# MCU_RF.net
KiCad netlist of a schematic drawn in Altium Designer
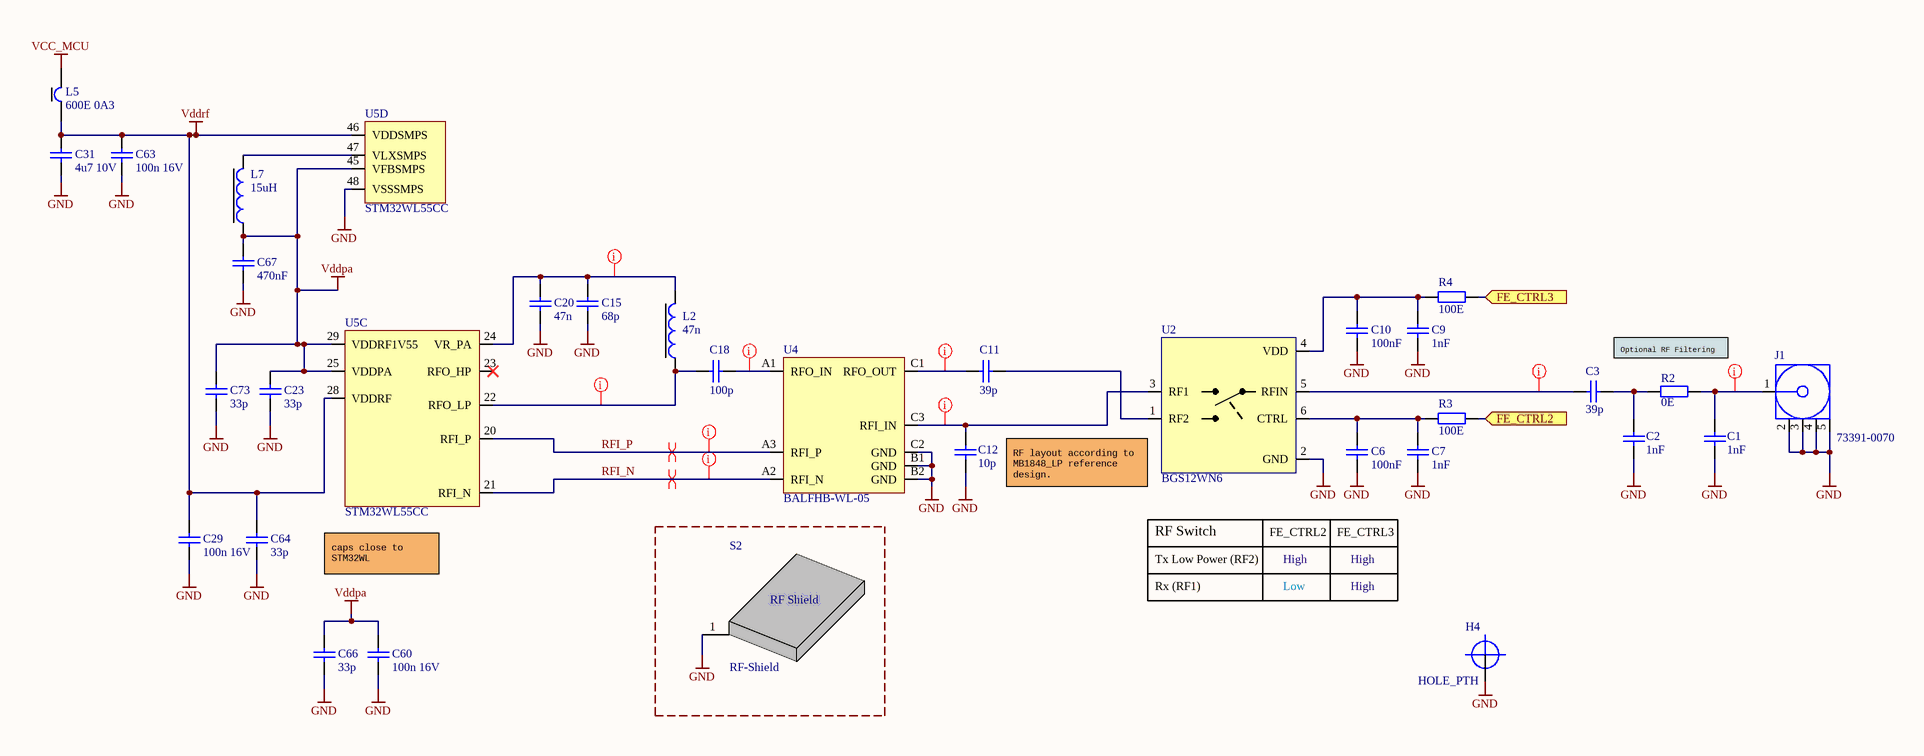
[diagram p0: MCU_RF.SchDoc]

(export (version "E")
  (design (tool "Eeschema 10.0.6"))
  (components
    (comp (ref "C1")
      (value "1nF")
      (footprint "CAP-000G001-002")
      (description "1nF 50V 10% X7R")
      (libsource (lib "DCI") (part "Capacitor_NP"))
    )
    (comp (ref "C2")
      (value "1nF")
      (footprint "CAP-000G001-002")
      (description "1nF 50V 10% X7R")
      (libsource (lib "DCI") (part "Capacitor_NP"))
    )
    (comp (ref "C3")
      (value "39p")
      (footprint "CAP-000G001-002")
      (description "39pF, 50V, 10%")
      (libsource (lib "DCI") (part "Capacitor_NP"))
    )
    (comp (ref "C6")
      (value "100nF")
      (footprint "CAP-000G001-002")
      (description "100nF, 10V, X5R")
      (libsource (lib "DCI") (part "Capacitor_NP"))
    )
    (comp (ref "C7")
      (value "1nF")
      (footprint "CAP-000G001-002")
      (description "1nF 50V 10% X7R")
      (libsource (lib "DCI") (part "Capacitor_NP"))
    )
    (comp (ref "C9")
      (value "1nF")
      (footprint "CAP-000G001-002")
      (description "1nF 50V 10% X7R")
      (libsource (lib "DCI") (part "Capacitor_NP"))
    )
    (comp (ref "C10")
      (value "100nF")
      (footprint "CAP-000G001-002")
      (description "100nF, 10V, X5R")
      (libsource (lib "DCI") (part "Capacitor_NP"))
    )
    (comp (ref "C11")
      (value "39p")
      (footprint "CAP-000G001-002")
      (description "39pF, 50V, 10%")
      (libsource (lib "DCI") (part "Capacitor_NP"))
    )
    (comp (ref "C12")
      (value "10p")
      (footprint "CAP-000G001-002")
      (description "10pF 50V 5% C0G/NP0")
      (libsource (lib "") (part "Capacitor_NP_1"))
    )
    (comp (ref "C15")
      (value "68p")
      (footprint "Cap-000G002-002")
      (description "68p 5% 25V C0G NP0")
      (libsource (lib "DCI") (part "Capacitor_NP"))
    )
    (comp (ref "C18")
      (value "100p")
      (footprint "CAP-000G001-002")
      (description "100pF, 50V, C0G")
      (libsource (lib "DCI") (part "Capacitor_NP"))
    )
    (comp (ref "C20")
      (value "47n")
      (footprint "Cap-000G002-002")
      (description "47NF, 50V, 10%")
      (libsource (lib "DCI") (part "Capacitor_NP"))
    )
    (comp (ref "C23")
      (value "33p")
      (footprint "CAP-000G001-002")
      (description "33pF, 25V, 5%")
      (libsource (lib "DCI") (part "Capacitor_NP"))
    )
    (comp (ref "C29")
      (value "100n 16V")
      (footprint "CAPC1005X05N")
      (description "100nF, 16V, 10%, X7R")
      (libsource (lib "DCI") (part "Capacitor_NP"))
    )
    (comp (ref "C31")
      (value "4u7 10V")
      (footprint "CAPC1608X09N")
      (description "4.7uF 10% 10V X5R")
      (libsource (lib "DCI") (part "Capacitor_NP"))
    )
    (comp (ref "C60")
      (value "100n 16V")
      (footprint "CAPC1005X05N")
      (description "100nF, 16V, 10%, X7R")
      (libsource (lib "DCI") (part "Capacitor_NP"))
    )
    (comp (ref "C63")
      (value "100n 16V")
      (footprint "CAPC1005X05N")
      (description "100nF, 16V, 10%, X7R")
      (libsource (lib "DCI") (part "Capacitor_NP"))
    )
    (comp (ref "C64")
      (value "33p")
      (footprint "CAP-000G001-002")
      (description "33pF, 25V, 5%")
      (libsource (lib "DCI") (part "Capacitor_NP"))
    )
    (comp (ref "C66")
      (value "33p")
      (footprint "CAP-000G001-002")
      (description "33pF, 25V, 5%")
      (libsource (lib "DCI") (part "Capacitor_NP"))
    )
    (comp (ref "C67")
      (value "470nF")
      (footprint "CAPC1608X09N")
      (description "470nF 16V ±10% X5R")
      (libsource (lib "DCI") (part "Capacitor_NP"))
    )
    (comp (ref "C73")
      (value "33p")
      (footprint "CAP-000G001-002")
      (description "33pF, 25V, 5%")
      (libsource (lib "DCI") (part "Capacitor_NP"))
    )
    (comp (ref "H4")
      (value "HOLE_PTH")
      (footprint "PTH_0.8_1.5")
      (libsource (lib "PCBComponenten") (part "HOLE_PTH"))
    )
    (comp (ref "J1")
      (value "73391-0070")
      (footprint "AMP-SMA-132134")
      (description "SMA Fem PCB vertical")
      (libsource (lib "DCI") (part "CN-1P-F-RF5"))
    )
    (comp (ref "L2")
      (value "47n")
      (footprint "IND-000G002-002")
      (description "47n 2% 210mA")
      (libsource (lib "DCI") (part "Inductor"))
    )
    (comp (ref "L5")
      (value "600E 0A3")
      (footprint "INDC1608X10N")
      (description "600E @100Mhz 0.3A")
      (libsource (lib "DCI") (part "ferrite"))
    )
    (comp (ref "L7")
      (value "15uH")
      (footprint "IND-000G004-002")
      (description "15uH 120mA")
      (libsource (lib "DCI") (part "Inductor"))
    )
    (comp (ref "R2")
      (value "0E")
      (footprint "RES-000G001-002")
      (description "0E 0.05W 1%")
      (libsource (lib "") (part "Resistor_1"))
    )
    (comp (ref "R3")
      (value "100E")
      (footprint "RES-000G001-002")
      (description "100E 0.05W 5% 100ppm")
      (libsource (lib "DCI") (part "Resistor"))
    )
    (comp (ref "R4")
      (value "100E")
      (footprint "RES-000G001-002")
      (description "100E 0.05W 5% 100ppm")
      (libsource (lib "DCI") (part "Resistor"))
    )
    (comp (ref "S2")
      (value "RF-Shield")
      (footprint "SHLD-000G000")
      (description "PCB SMD shield")
      (fields
        (field (name "MANUFACTURER") "Masach Tech")
        (field (name "MANUFACTURER_PART_NUMBER") "MS409-10")
      )
      (libsource (lib "DCI") (part "RF-Shield"))
    )
    (comp (ref "U2")
      (value "BGS12WN6")
      (footprint "DFN-400G001-006")
      (description "RF-switch")
      (fields (field (name "MANUFACTURER_PART_NUMBER") "BGS12SN6") (field (name "MANUFACTURER") "INFINEON"))
      (libsource (lib "DCI") (part "IC_BGS12SN6_PG-TSNP-6-1"))
    )
    (comp (ref "U4")
      (value "BALFHB-WL-05")
      (footprint "BGA-690G001-008")
      (description "Balun")
      (fields
        (field (name "MANUFACTURER") "STMICROELECTRONICS")
        (field (name "MANUFACTURER_PART_NUMBER") "IPD STM STM32WL")
      )
      (libsource (lib "DCI") (part "balun_BALFHB-WL-05D3"))
    )
    (comp (ref "U5")
      (value "STM32WL55CC")
      (footprint "QFN-500G000-048")
      (libsource (lib "DCI") (part "STM32WL55"))
    )
  )
  (nets
    (net (code "1") (name "/FE_CTRL2") (class "Default")
      (node (ref "R3") (pin "2") (pinfunction "2_2") (pintype "passive"))
    )
    (net (code "2") (name "/FE_CTRL3") (class "Default")
      (node (ref "R4") (pin "2") (pinfunction "2_2") (pintype "passive"))
    )
    (net (code "3") (name "/RFI_N") (class "Default")
      (node (ref "U4") (pin "A2") (pinfunction "RFI_N_A2") (pintype "passive"))
      (node (ref "U5") (pin "21") (pinfunction "RFI_N_21") (pintype "passive"))
    )
    (net (code "4") (name "/RFI_P") (class "Default")
      (node (ref "U4") (pin "A3") (pinfunction "RFI_P_A3") (pintype "passive"))
      (node (ref "U5") (pin "20") (pinfunction "RFI_P_20") (pintype "passive"))
    )
    (net (code "5") (name "GND") (class "Default")
      (node (ref "C1") (pin "1") (pinfunction "1_1") (pintype "passive"))
      (node (ref "C10") (pin "1") (pinfunction "1_1") (pintype "passive"))
      (node (ref "C12") (pin "1") (pinfunction "1_1") (pintype "passive"))
      (node (ref "C15") (pin "1") (pinfunction "1_1") (pintype "passive"))
      (node (ref "C2") (pin "1") (pinfunction "1_1") (pintype "passive"))
      (node (ref "C20") (pin "1") (pinfunction "1_1") (pintype "passive"))
      (node (ref "C23") (pin "1") (pinfunction "1_1") (pintype "passive"))
      (node (ref "C29") (pin "1") (pinfunction "1_1") (pintype "passive"))
      (node (ref "C31") (pin "1") (pinfunction "1_1") (pintype "passive"))
      (node (ref "C6") (pin "1") (pinfunction "1_1") (pintype "passive"))
      (node (ref "C60") (pin "1") (pinfunction "1_1") (pintype "passive"))
      (node (ref "C63") (pin "1") (pinfunction "1_1") (pintype "passive"))
      (node (ref "C64") (pin "1") (pinfunction "1_1") (pintype "passive"))
      (node (ref "C66") (pin "1") (pinfunction "1_1") (pintype "passive"))
      (node (ref "C67") (pin "1") (pinfunction "1_1") (pintype "passive"))
      (node (ref "C7") (pin "1") (pinfunction "1_1") (pintype "passive"))
      (node (ref "C73") (pin "1") (pinfunction "1_1") (pintype "passive"))
      (node (ref "C9") (pin "1") (pinfunction "1_1") (pintype "passive"))
      (node (ref "H4") (pin "0") (pinfunction "0_0") (pintype "passive"))
      (node (ref "J1") (pin "2") (pinfunction "GND_2") (pintype "power_in"))
      (node (ref "J1") (pin "3") (pinfunction "GND_3") (pintype "power_in"))
      (node (ref "J1") (pin "4") (pinfunction "GND_4") (pintype "power_in"))
      (node (ref "J1") (pin "5") (pinfunction "GND_5") (pintype "power_in"))
      (node (ref "S2") (pin "1") (pinfunction "1_1") (pintype "passive"))
      (node (ref "U2") (pin "2") (pinfunction "GND_2") (pintype "passive"))
      (node (ref "U4") (pin "B1") (pinfunction "GND_B1") (pintype "passive"))
      (node (ref "U4") (pin "B2") (pinfunction "GND_B2") (pintype "passive"))
      (node (ref "U4") (pin "C2") (pinfunction "GND_C2") (pintype "power_in"))
      (node (ref "U5") (pin "48") (pinfunction "VSSSMPS_48") (pintype "passive"))
    )
    (net (code "6") (name "Net-(C2-Pad2)") (class "Default")
      (node (ref "C2") (pin "2") (pinfunction "2_2") (pintype "passive"))
      (node (ref "C3") (pin "1") (pinfunction "1_1") (pintype "passive"))
      (node (ref "R2") (pin "2") (pinfunction "2_2") (pintype "passive"))
    )
    (net (code "7") (name "Net-(J1-Signal)") (class "Default")
      (node (ref "C1") (pin "2") (pinfunction "2_2") (pintype "passive"))
      (node (ref "J1") (pin "1") (pinfunction "Signal_1") (pintype "passive"))
      (node (ref "R2") (pin "1") (pinfunction "1_1") (pintype "passive"))
    )
    (net (code "8") (name "Net-(U2-CTRL)") (class "Default")
      (node (ref "C6") (pin "2") (pinfunction "2_2") (pintype "passive"))
      (node (ref "C7") (pin "2") (pinfunction "2_2") (pintype "passive"))
      (node (ref "R3") (pin "1") (pinfunction "1_1") (pintype "passive"))
      (node (ref "U2") (pin "6") (pinfunction "CTRL_6") (pintype "passive"))
    )
    (net (code "9") (name "Net-(U2-RF1)") (class "Default")
      (node (ref "C12") (pin "2") (pinfunction "2_2") (pintype "passive"))
      (node (ref "U2") (pin "3") (pinfunction "RF1_3") (pintype "passive"))
      (node (ref "U4") (pin "C3") (pinfunction "RFI_IN_C3") (pintype "passive"))
    )
    (net (code "10") (name "Net-(U2-RF2)") (class "Default")
      (node (ref "C11") (pin "2") (pinfunction "2_2") (pintype "passive"))
      (node (ref "U2") (pin "1") (pinfunction "RF2_1") (pintype "passive"))
    )
    (net (code "11") (name "Net-(U2-RFIN)") (class "Default")
      (node (ref "C3") (pin "2") (pinfunction "2_2") (pintype "passive"))
      (node (ref "U2") (pin "5") (pinfunction "RFIN_5") (pintype "passive"))
    )
    (net (code "12") (name "Net-(U2-VDD)") (class "Default")
      (node (ref "C10") (pin "2") (pinfunction "2_2") (pintype "passive"))
      (node (ref "C9") (pin "2") (pinfunction "2_2") (pintype "passive"))
      (node (ref "R4") (pin "1") (pinfunction "1_1") (pintype "passive"))
      (node (ref "U2") (pin "4") (pinfunction "VDD_4") (pintype "passive"))
    )
    (net (code "13") (name "Net-(U4-RFO_IN)") (class "Default")
      (node (ref "C18") (pin "2") (pinfunction "2_2") (pintype "passive"))
      (node (ref "U4") (pin "A1") (pinfunction "RFO_IN_A1") (pintype "passive"))
    )
    (net (code "14") (name "Net-(U4-RFO_OUT)") (class "Default")
      (node (ref "C11") (pin "1") (pinfunction "1_1") (pintype "passive"))
      (node (ref "U4") (pin "C1") (pinfunction "RFO_OUT_C1") (pintype "passive"))
    )
    (net (code "15") (name "Net-(U5C-RFO_LP)") (class "Default")
      (node (ref "C18") (pin "1") (pinfunction "1_1") (pintype "passive"))
      (node (ref "L2") (pin "1") (pinfunction "1_1") (pintype "passive"))
      (node (ref "U5") (pin "22") (pinfunction "RFO_LP_22") (pintype "passive"))
    )
    (net (code "16") (name "Net-(U5C-VR_PA)") (class "Default")
      (node (ref "C15") (pin "2") (pinfunction "2_2") (pintype "passive"))
      (node (ref "C20") (pin "2") (pinfunction "2_2") (pintype "passive"))
      (node (ref "L2") (pin "2") (pinfunction "2_2") (pintype "passive"))
      (node (ref "U5") (pin "24") (pinfunction "VR_PA_24") (pintype "passive"))
    )
    (net (code "17") (name "Net-(U5D-VLXSMPS)") (class "Default")
      (node (ref "L7") (pin "2") (pinfunction "2_2") (pintype "passive"))
      (node (ref "U5") (pin "47") (pinfunction "VLXSMPS_47") (pintype "passive"))
    )
    (net (code "18") (name "VCC_MCU") (class "Default")
      (node (ref "L5") (pin "2") (pinfunction "2_2") (pintype "passive"))
    )
    (net (code "19") (name "Vddpa") (class "Default")
      (node (ref "C23") (pin "2") (pinfunction "2_2") (pintype "passive"))
      (node (ref "C60") (pin "2") (pinfunction "2_2") (pintype "passive"))
      (node (ref "C66") (pin "2") (pinfunction "2_2") (pintype "passive"))
      (node (ref "C67") (pin "2") (pinfunction "2_2") (pintype "passive"))
      (node (ref "C73") (pin "2") (pinfunction "2_2") (pintype "passive"))
      (node (ref "L7") (pin "1") (pinfunction "1_1") (pintype "passive"))
      (node (ref "U5") (pin "25") (pinfunction "VDDPA_25") (pintype "passive"))
      (node (ref "U5") (pin "29") (pinfunction "VDDRF1V55_29") (pintype "passive"))
      (node (ref "U5") (pin "45") (pinfunction "VFBSMPS_45") (pintype "passive"))
    )
    (net (code "20") (name "Vddrf") (class "Default")
      (node (ref "C29") (pin "2") (pinfunction "2_2") (pintype "passive"))
      (node (ref "C31") (pin "2") (pinfunction "2_2") (pintype "passive"))
      (node (ref "C63") (pin "2") (pinfunction "2_2") (pintype "passive"))
      (node (ref "C64") (pin "2") (pinfunction "2_2") (pintype "passive"))
      (node (ref "L5") (pin "1") (pinfunction "1_1") (pintype "passive"))
      (node (ref "U5") (pin "28") (pinfunction "VDDRF_28") (pintype "passive"))
      (node (ref "U5") (pin "46") (pinfunction "VDDSMPS_46") (pintype "passive"))
    )
    (net (code "21") (name "unconnected-(U5C-RFO_HP-Pad23)") (class "Default")
      (node (ref "U5") (pin "23") (pinfunction "RFO_HP_23") (pintype "passive+no_connect"))
    )
  )
)
